# Sheet1.net
KiCad netlist of a schematic drawn in Altium Designer
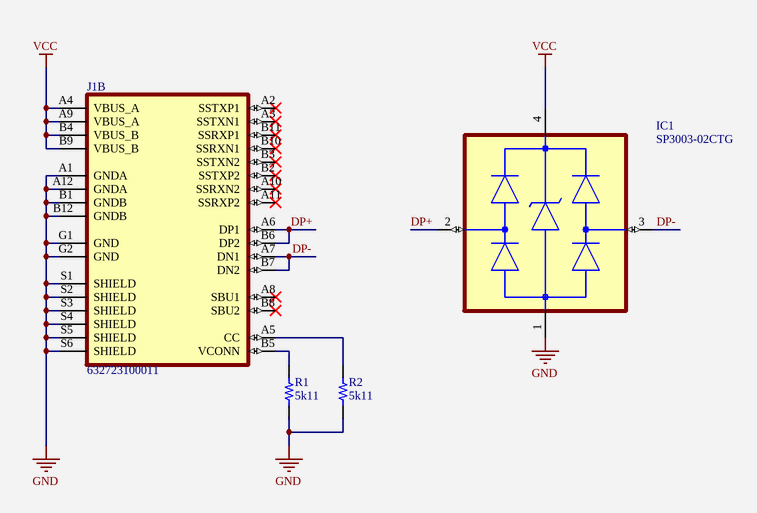
[diagram p0: Sheet1.SchDoc]

(export (version "E")
  (design (tool "Eeschema 10.0.6"))
  (components
    (comp (ref "IC1")
      (value "SP3003-02CTG")
      (footprint "Littelfuse_SR05_MFG")
      (description "SR05 Series 5V 25A")
      (libsource (lib "IntegLib_Sceric") (part "SP3003-02CTG"))
    )
    (comp (ref "J1")
      (value "632723100011")
      (footprint "WURTH_632723100011")
      (fields (field (name "MF") "Wurth Electronics"))
      (libsource (lib "IntegLib_Sceric") (part "632723100011"))
    )
    (comp (ref "R1")
      (value "5k11")
      (footprint "0603_R")
      (description "5k11,  1% , 100ppm, 0.100W, 0603, SMD")
      (fields (field (name "PART NUMBER") "RC0603FR-075K11L") (field (name "MANUFACTURER") "Yageo"))
      (libsource (lib "IntegLib_Sceric") (part "RC0603FR-075K11L"))
    )
    (comp (ref "R2")
      (value "5k11")
      (footprint "0603_R")
      (description "5k11,  1% , 100ppm, 0.100W, 0603, SMD")
      (fields (field (name "PART NUMBER") "RC0603FR-075K11L") (field (name "MANUFACTURER") "Yageo"))
      (libsource (lib "IntegLib_Sceric") (part "RC0603FR-075K11L"))
    )
  )
  (nets
    (net (code "1") (name "/DP+") (class "Default")
      (node (ref "IC1") (pin "2") (pinfunction "I/O_1_2") (pintype "bidirectional"))
      (node (ref "J1") (pin "A6") (pinfunction "DP1_A6") (pintype "bidirectional"))
      (node (ref "J1") (pin "B6") (pinfunction "DP2_B6") (pintype "bidirectional"))
    )
    (net (code "2") (name "/DP-") (class "Default")
      (node (ref "IC1") (pin "3") (pinfunction "I/O_2_3") (pintype "bidirectional"))
      (node (ref "J1") (pin "A7") (pinfunction "DN1_A7") (pintype "bidirectional"))
      (node (ref "J1") (pin "B7") (pinfunction "DN2_B7") (pintype "bidirectional"))
    )
    (net (code "3") (name "GND") (class "Default")
      (node (ref "IC1") (pin "1") (pinfunction "GND_1") (pintype "power_in"))
      (node (ref "J1") (pin "A1") (pinfunction "GNDA_A1") (pintype "power_in"))
      (node (ref "J1") (pin "A12") (pinfunction "GNDA_A12") (pintype "power_in"))
      (node (ref "J1") (pin "B1") (pinfunction "GNDB_B1") (pintype "power_in"))
      (node (ref "J1") (pin "B12") (pinfunction "GNDB_B12") (pintype "power_in"))
      (node (ref "J1") (pin "G1") (pinfunction "GND_G1") (pintype "power_in"))
      (node (ref "J1") (pin "G2") (pinfunction "GND_G2") (pintype "power_in"))
      (node (ref "J1") (pin "S1") (pinfunction "SHIELD_S1") (pintype "passive"))
      (node (ref "J1") (pin "S2") (pinfunction "SHIELD_S2") (pintype "passive"))
      (node (ref "J1") (pin "S3") (pinfunction "SHIELD_S3") (pintype "passive"))
      (node (ref "J1") (pin "S4") (pinfunction "SHIELD_S4") (pintype "passive"))
      (node (ref "J1") (pin "S5") (pinfunction "SHIELD_S5") (pintype "passive"))
      (node (ref "J1") (pin "S6") (pinfunction "SHIELD_S6") (pintype "passive"))
      (node (ref "R1") (pin "1") (pinfunction "1_1") (pintype "passive"))
      (node (ref "R2") (pin "1") (pinfunction "1_1") (pintype "passive"))
    )
    (net (code "4") (name "Net-(J1B-CC)") (class "Default")
      (node (ref "J1") (pin "A5") (pinfunction "CC_A5") (pintype "bidirectional"))
      (node (ref "R2") (pin "2") (pinfunction "2_2") (pintype "passive"))
    )
    (net (code "5") (name "Net-(J1B-VCONN)") (class "Default")
      (node (ref "J1") (pin "B5") (pinfunction "VCONN_B5") (pintype "bidirectional"))
      (node (ref "R1") (pin "2") (pinfunction "2_2") (pintype "passive"))
    )
    (net (code "6") (name "VCC") (class "Default")
      (node (ref "IC1") (pin "4") (pinfunction "VCC_4") (pintype "power_in"))
      (node (ref "J1") (pin "A4") (pinfunction "VBUS_A_A4") (pintype "power_in"))
      (node (ref "J1") (pin "A9") (pinfunction "VBUS_A_A9") (pintype "power_in"))
      (node (ref "J1") (pin "B4") (pinfunction "VBUS_B_B4") (pintype "power_in"))
      (node (ref "J1") (pin "B9") (pinfunction "VBUS_B_B9") (pintype "power_in"))
    )
    (net (code "7") (name "unconnected-(J1B-SBU1-PadA8)") (class "Default")
      (node (ref "J1") (pin "A8") (pinfunction "SBU1_A8") (pintype "bidirectional+no_connect"))
    )
    (net (code "8") (name "unconnected-(J1B-SBU2-PadB8)") (class "Default")
      (node (ref "J1") (pin "B8") (pinfunction "SBU2_B8") (pintype "bidirectional+no_connect"))
    )
    (net (code "9") (name "unconnected-(J1B-SSRXN1-PadB10)") (class "Default")
      (node (ref "J1") (pin "B10") (pinfunction "SSRXN1_B10") (pintype "bidirectional+no_connect"))
    )
    (net (code "10") (name "unconnected-(J1B-SSRXN2-PadA10)") (class "Default")
      (node (ref "J1") (pin "A10") (pinfunction "SSRXN2_A10") (pintype "bidirectional+no_connect"))
    )
    (net (code "11") (name "unconnected-(J1B-SSRXP1-PadB11)") (class "Default")
      (node (ref "J1") (pin "B11") (pinfunction "SSRXP1_B11") (pintype "bidirectional+no_connect"))
    )
    (net (code "12") (name "unconnected-(J1B-SSRXP2-PadA11)") (class "Default")
      (node (ref "J1") (pin "A11") (pinfunction "SSRXP2_A11") (pintype "bidirectional+no_connect"))
    )
    (net (code "13") (name "unconnected-(J1B-SSTXN1-PadA3)") (class "Default")
      (node (ref "J1") (pin "A3") (pinfunction "SSTXN1_A3") (pintype "bidirectional+no_connect"))
    )
    (net (code "14") (name "unconnected-(J1B-SSTXN2-PadB3)") (class "Default")
      (node (ref "J1") (pin "B3") (pinfunction "SSTXN2_B3") (pintype "bidirectional+no_connect"))
    )
    (net (code "15") (name "unconnected-(J1B-SSTXP1-PadA2)") (class "Default")
      (node (ref "J1") (pin "A2") (pinfunction "SSTXP1_A2") (pintype "bidirectional+no_connect"))
    )
    (net (code "16") (name "unconnected-(J1B-SSTXP2-PadB2)") (class "Default")
      (node (ref "J1") (pin "B2") (pinfunction "SSTXP2_B2") (pintype "bidirectional+no_connect"))
    )
  )
)
